# Remote_nodeIO_Hardware.net
KiCad netlist of a schematic drawn in EasyEDA Pro
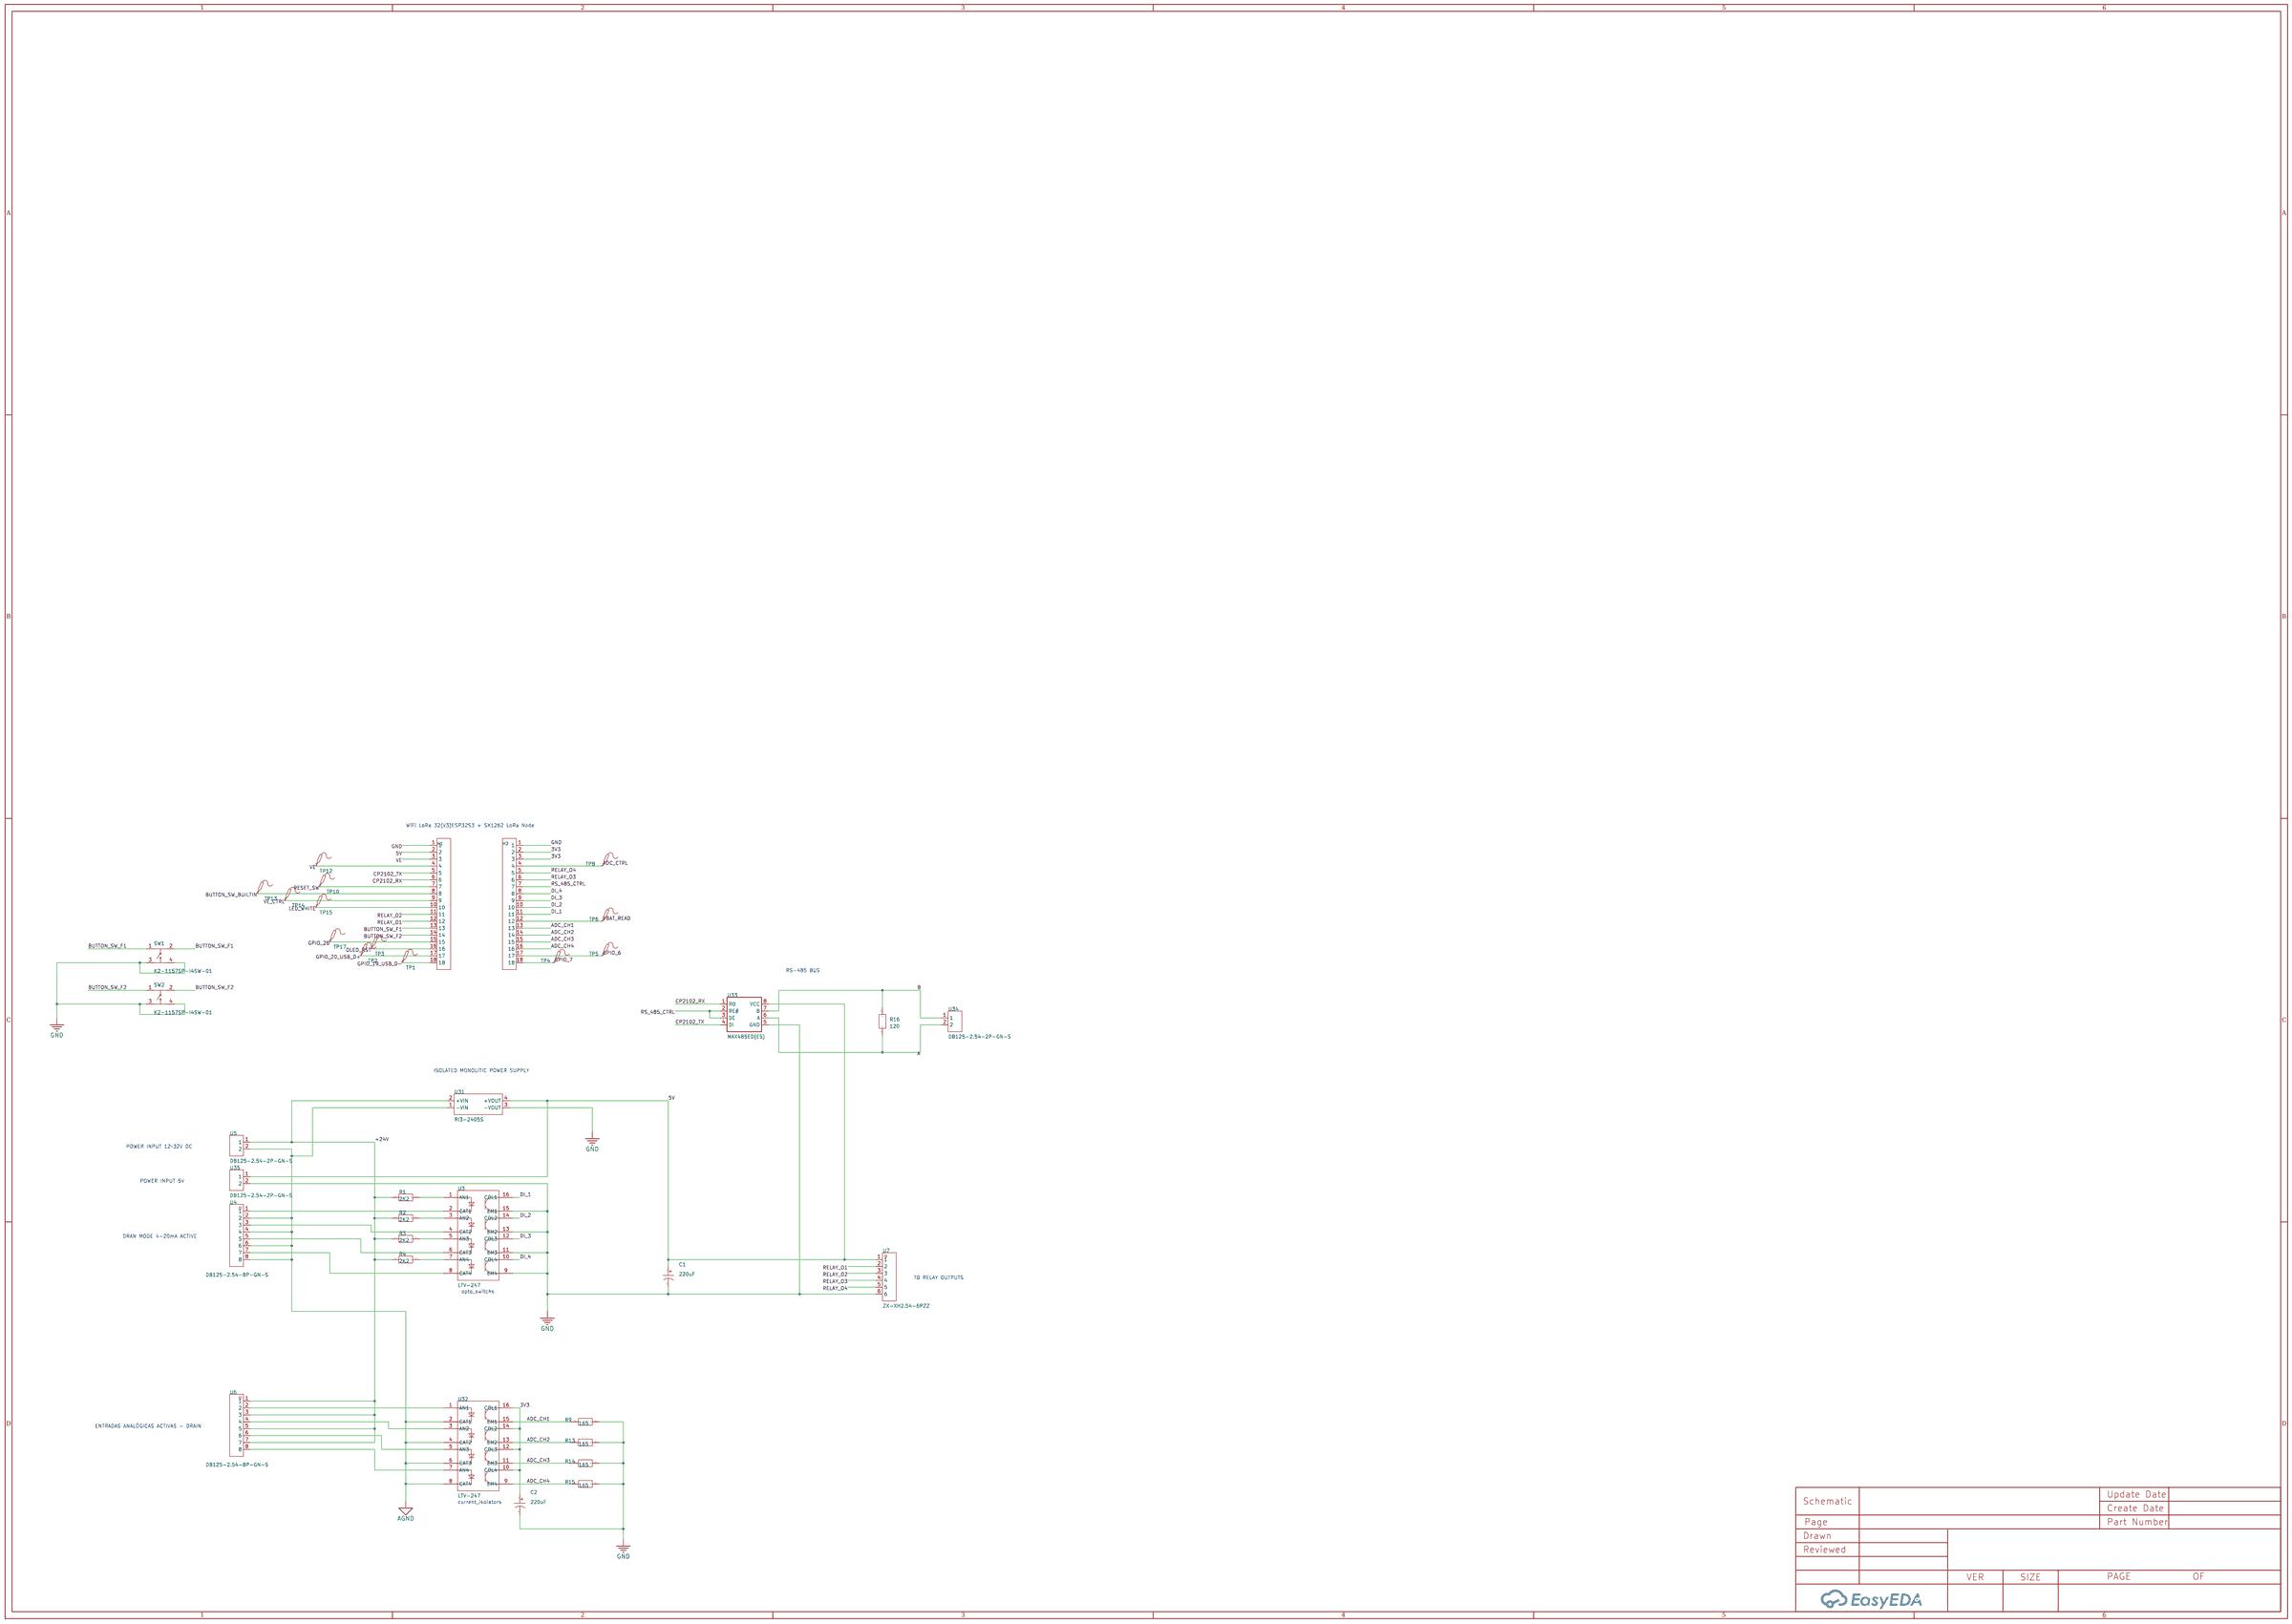
[diagram p0: schematic sheet]

(export (version "E")
  (design (tool "Eeschema 10.0.6"))
  (components
    (comp (ref "C1")
      (value "220uF")
      (footprint "easyedapro:CAP-SMD_BD6.3-L6.6-W6.6-FD")
      (fields (field (name "Manufacturer Part") "RVT1A221M0605") (field (name "Manufacturer") "ROQANG(容强)"))
      (libsource (lib "easyedapro") (part "RVT1A221M0605-C72494"))
    )
    (comp (ref "C2")
      (value "220uF")
      (footprint "easyedapro:CAP-SMD_BD6.3-L6.6-W6.6-FD")
      (fields (field (name "Manufacturer Part") "RVT1A221M0605") (field (name "Manufacturer") "ROQANG(容强)"))
      (libsource (lib "easyedapro") (part "RVT1A221M0605-C72494"))
    )
    (comp (ref "H1")
      (value "PM254-1-18-Z-8.5")
      (footprint "easyedapro:HDR-TH_18P-P2.54-V-F")
      (fields (field (name "Manufacturer") "HCTL(华灿天禄)"))
      (libsource (lib "easyedapro") (part "PM254-1-18-Z-8.5_C3012090"))
    )
    (comp (ref "H2")
      (value "PM254-1-18-Z-8.5")
      (footprint "easyedapro:HDR-TH_18P-P2.54-V-F")
      (fields (field (name "Manufacturer") "HCTL(华灿天禄)"))
      (libsource (lib "easyedapro") (part "PM254-1-18-Z-8.5_C3012090"))
    )
    (comp (ref "R1")
      (value "2K2")
      (footprint "easyedapro:R1206")
      (fields
        (field (name "Manufacturer Part") "AS0606J036JT5E")
        (field (name "Manufacturer") "UNI-ROYAL(厚声)")
      )
      (libsource (lib "easyedapro") (part "AS0606J036JT5E"))
    )
    (comp (ref "R2")
      (value "2K2")
      (footprint "easyedapro:R1206")
      (fields
        (field (name "Manufacturer Part") "AS0606J036JT5E")
        (field (name "Manufacturer") "UNI-ROYAL(厚声)")
      )
      (libsource (lib "easyedapro") (part "AS0606J036JT5E"))
    )
    (comp (ref "R3")
      (value "2K2")
      (footprint "easyedapro:R1206")
      (fields
        (field (name "Manufacturer Part") "AS0606J036JT5E")
        (field (name "Manufacturer") "UNI-ROYAL(厚声)")
      )
      (libsource (lib "easyedapro") (part "AS0606J036JT5E"))
    )
    (comp (ref "R4")
      (value "2K2")
      (footprint "easyedapro:R1206")
      (fields
        (field (name "Manufacturer Part") "AS0606J036JT5E")
        (field (name "Manufacturer") "UNI-ROYAL(厚声)")
      )
      (libsource (lib "easyedapro") (part "AS0606J036JT5E"))
    )
    (comp (ref "R9")
      (value "165")
      (footprint "easyedapro:R1206")
      (fields
        (field (name "Manufacturer Part") "AS0606J036JT5E")
        (field (name "Manufacturer") "UNI-ROYAL(厚声)")
      )
      (libsource (lib "easyedapro") (part "AS0606J036JT5E"))
    )
    (comp (ref "R13")
      (value "165")
      (footprint "easyedapro:R1206")
      (fields
        (field (name "Manufacturer Part") "AS0606J036JT5E")
        (field (name "Manufacturer") "UNI-ROYAL(厚声)")
      )
      (libsource (lib "easyedapro") (part "AS0606J036JT5E"))
    )
    (comp (ref "R14")
      (value "165")
      (footprint "easyedapro:R1206")
      (fields
        (field (name "Manufacturer Part") "AS0606J036JT5E")
        (field (name "Manufacturer") "UNI-ROYAL(厚声)")
      )
      (libsource (lib "easyedapro") (part "AS0606J036JT5E"))
    )
    (comp (ref "R15")
      (value "165")
      (footprint "easyedapro:R1206")
      (fields
        (field (name "Manufacturer Part") "AS0606J036JT5E")
        (field (name "Manufacturer") "UNI-ROYAL(厚声)")
      )
      (libsource (lib "easyedapro") (part "AS0606J036JT5E"))
    )
    (comp (ref "R16")
      (value "120")
      (footprint "easyedapro:R1206")
      (fields
        (field (name "Manufacturer Part") "AS0606J036JT5E")
        (field (name "Manufacturer") "UNI-ROYAL(厚声)")
      )
      (libsource (lib "easyedapro") (part "AS0606J036JT5E"))
    )
    (comp (ref "SW1")
      (value "K2-1157SP-I4SW-01")
      (footprint "easyedapro:SW-SMD_4P-L6.2-W6.2-P4.50-LS8.6")
      (fields (field (name "Manufacturer") "韩国韩荣"))
      (libsource (lib "easyedapro") (part "K2-1157SP-I4SW-04"))
    )
    (comp (ref "SW2")
      (value "K2-1157SP-I4SW-01")
      (footprint "easyedapro:SW-SMD_4P-L6.2-W6.2-P4.50-LS8.6")
      (fields (field (name "Manufacturer") "韩国韩荣"))
      (libsource (lib "easyedapro") (part "K2-1157SP-I4SW-04"))
    )
    (comp (ref "TP1")
      (value "~")
      (footprint "easyedapro:Test-Point-0.5mm")
      (description "Test Point 测试点")
      (libsource (lib "easyedapro") (part "Test-Point"))
    )
    (comp (ref "TP2")
      (value "~")
      (footprint "easyedapro:Test-Point-0.5mm")
      (description "Test Point 测试点")
      (libsource (lib "easyedapro") (part "Test-Point"))
    )
    (comp (ref "TP3")
      (value "~")
      (footprint "easyedapro:Test-Point-0.5mm")
      (description "Test Point 测试点")
      (libsource (lib "easyedapro") (part "Test-Point"))
    )
    (comp (ref "TP4")
      (value "~")
      (footprint "easyedapro:Test-Point-0.5mm")
      (description "Test Point 测试点")
      (libsource (lib "easyedapro") (part "Test-Point"))
    )
    (comp (ref "TP5")
      (value "~")
      (footprint "easyedapro:Test-Point-0.5mm")
      (description "Test Point 测试点")
      (libsource (lib "easyedapro") (part "Test-Point"))
    )
    (comp (ref "TP6")
      (value "~")
      (footprint "easyedapro:Test-Point-0.5mm")
      (description "Test Point 测试点")
      (libsource (lib "easyedapro") (part "Test-Point"))
    )
    (comp (ref "TP8")
      (value "~")
      (footprint "easyedapro:Test-Point-0.5mm")
      (description "Test Point 测试点")
      (libsource (lib "easyedapro") (part "Test-Point"))
    )
    (comp (ref "TP10")
      (value "~")
      (footprint "easyedapro:Test-Point-0.5mm")
      (description "Test Point 测试点")
      (libsource (lib "easyedapro") (part "Test-Point"))
    )
    (comp (ref "TP12")
      (value "~")
      (footprint "easyedapro:Test-Point-0.5mm")
      (description "Test Point 测试点")
      (libsource (lib "easyedapro") (part "Test-Point"))
    )
    (comp (ref "TP13")
      (value "~")
      (footprint "easyedapro:Test-Point-0.5mm")
      (description "Test Point 测试点")
      (libsource (lib "easyedapro") (part "Test-Point"))
    )
    (comp (ref "TP14")
      (value "~")
      (footprint "easyedapro:Test-Point-0.5mm")
      (description "Test Point 测试点")
      (libsource (lib "easyedapro") (part "Test-Point"))
    )
    (comp (ref "TP15")
      (value "~")
      (footprint "easyedapro:Test-Point-0.5mm")
      (description "Test Point 测试点")
      (libsource (lib "easyedapro") (part "Test-Point"))
    )
    (comp (ref "TP17")
      (value "~")
      (footprint "easyedapro:Test-Point-0.5mm")
      (description "Test Point 测试点")
      (libsource (lib "easyedapro") (part "Test-Point"))
    )
    (comp (ref "U3")
      (value "LTV-247")
      (footprint "easyedapro:SOP-16_L10.3-W5.4-P1.27-LS7.8-BL")
      (fields (field (name "Manufacturer") "LITEON(光宝)"))
      (libsource (lib "easyedapro") (part "LTV-247"))
    )
    (comp (ref "U4")
      (value "DB125-2.54-8P-GN-S")
      (footprint "easyedapro:CONN-TH_DB125-2.54-8P-GN")
      (fields (field (name "Manufacturer") "DORABO(地博电气)"))
      (libsource (lib "easyedapro") (part "DB125-2.54-8P-GN"))
    )
    (comp (ref "U5")
      (value "DB125-2.54-2P-GN-S")
      (footprint "easyedapro:CONN-TH_DB125-2.54-2P-GN")
      (fields (field (name "Manufacturer") "DORABO(地博电气)"))
      (libsource (lib "easyedapro") (part "DB125-2.54-2P-GN"))
    )
    (comp (ref "U6")
      (value "DB125-2.54-8P-GN-S")
      (footprint "easyedapro:CONN-TH_DB125-2.54-8P-GN")
      (fields (field (name "Manufacturer") "DORABO(地博电气)"))
      (libsource (lib "easyedapro") (part "DB125-2.54-8P-GN"))
    )
    (comp (ref "U7")
      (value "ZX-XH2.54-6PZZ")
      (footprint "easyedapro:CONN-TH_6P-P2.50_ZX-XH2.54-6PZZ")
      (fields (field (name "Manufacturer") "Megastar(兆星)"))
      (libsource (lib "easyedapro") (part "ZX-XH2.54-6PZZ"))
    )
    (comp (ref "U31")
      (value "RI3-2405S")
      (footprint "easyedapro:PWRM-TH_RI3-XXXXS")
      (fields (field (name "Manufacturer") "Recom Power"))
      (libsource (lib "easyedapro") (part "RI3-2405S"))
    )
    (comp (ref "U32")
      (value "LTV-247")
      (footprint "easyedapro:SOP-16_L10.3-W5.4-P1.27-LS7.8-BL")
      (fields (field (name "Manufacturer") "LITEON(光宝)"))
      (libsource (lib "easyedapro") (part "LTV-247"))
    )
    (comp (ref "U33")
      (value "MAX485ED(ES)")
      (footprint "easyedapro:SOIC-8_L5.0-W4.0-P1.27-LS6.0-BL")
      (fields (field (name "Manufacturer") "ElecSuper(静芯)"))
      (libsource (lib "easyedapro") (part "MAX485ED(ES)"))
    )
    (comp (ref "U34")
      (value "DB125-2.54-2P-GN-S")
      (footprint "easyedapro:CONN-TH_DB125-2.54-2P-GN")
      (fields (field (name "Manufacturer") "DORABO(地博电气)"))
      (libsource (lib "easyedapro") (part "DB125-2.54-2P-GN"))
    )
    (comp (ref "U35")
      (value "DB125-2.54-2P-GN-S")
      (footprint "easyedapro:CONN-TH_DB125-2.54-2P-GN")
      (fields (field (name "Manufacturer") "DORABO(地博电气)"))
      (libsource (lib "easyedapro") (part "DB125-2.54-2P-GN"))
    )
  )
  (nets
    (net (code "1") (name "/+24V") (class "Default")
      (node (ref "R1") (pin "1") (pinfunction "1_1") (pintype "unspecified"))
      (node (ref "R2") (pin "1") (pinfunction "1_1") (pintype "unspecified"))
      (node (ref "R3") (pin "1") (pinfunction "1_1") (pintype "unspecified"))
      (node (ref "R4") (pin "1") (pinfunction "1_1") (pintype "unspecified"))
      (node (ref "U31") (pin "2") (pinfunction "+VIN_2") (pintype "unspecified"))
      (node (ref "U5") (pin "1") (pinfunction "1_1") (pintype "unspecified"))
      (node (ref "U6") (pin "1") (pinfunction "1_1") (pintype "unspecified"))
      (node (ref "U6") (pin "3") (pinfunction "3_3") (pintype "unspecified"))
      (node (ref "U6") (pin "5") (pinfunction "5_5") (pintype "unspecified"))
      (node (ref "U6") (pin "7") (pinfunction "7_7") (pintype "unspecified"))
    )
    (net (code "2") (name "/3V3") (class "Default")
      (node (ref "C2") (pin "1") (pinfunction "1_1") (pintype "input"))
      (node (ref "H2") (pin "2") (pinfunction "2_2") (pintype "unspecified"))
      (node (ref "H2") (pin "3") (pinfunction "3_3") (pintype "unspecified"))
      (node (ref "U32") (pin "10") (pinfunction "COL4_10") (pintype "unspecified"))
      (node (ref "U32") (pin "12") (pinfunction "COL3_12") (pintype "unspecified"))
      (node (ref "U32") (pin "14") (pinfunction "COL2_14") (pintype "unspecified"))
      (node (ref "U32") (pin "16") (pinfunction "COL1_16") (pintype "unspecified"))
    )
    (net (code "3") (name "/5V") (class "Default")
      (node (ref "C1") (pin "1") (pinfunction "1_1") (pintype "input"))
      (node (ref "H1") (pin "2") (pinfunction "2_2") (pintype "unspecified"))
      (node (ref "U31") (pin "4") (pinfunction "+VOUT_4") (pintype "unspecified"))
      (node (ref "U33") (pin "8") (pinfunction "VCC_8") (pintype "unspecified"))
      (node (ref "U35") (pin "1") (pinfunction "1_1") (pintype "unspecified"))
      (node (ref "U7") (pin "1") (pinfunction "1_1") (pintype "unspecified"))
    )
    (net (code "4") (name "/A") (class "Default")
      (node (ref "R16") (pin "1") (pinfunction "1_1") (pintype "unspecified"))
      (node (ref "U33") (pin "6") (pinfunction "A_6") (pintype "unspecified"))
      (node (ref "U34") (pin "2") (pinfunction "2_2") (pintype "unspecified"))
    )
    (net (code "5") (name "/ADC_CH1") (class "Default")
      (node (ref "H2") (pin "13") (pinfunction "13_13") (pintype "unspecified"))
      (node (ref "R9") (pin "1") (pinfunction "1_1") (pintype "unspecified"))
      (node (ref "U32") (pin "15") (pinfunction "EM1_15") (pintype "unspecified"))
    )
    (net (code "6") (name "/ADC_CH2") (class "Default")
      (node (ref "H2") (pin "14") (pinfunction "14_14") (pintype "unspecified"))
      (node (ref "R13") (pin "1") (pinfunction "1_1") (pintype "unspecified"))
      (node (ref "U32") (pin "13") (pinfunction "EM2_13") (pintype "unspecified"))
    )
    (net (code "7") (name "/ADC_CH3") (class "Default")
      (node (ref "H2") (pin "15") (pinfunction "15_15") (pintype "unspecified"))
      (node (ref "R14") (pin "1") (pinfunction "1_1") (pintype "unspecified"))
      (node (ref "U32") (pin "11") (pinfunction "EM3_11") (pintype "unspecified"))
    )
    (net (code "8") (name "/ADC_CH4") (class "Default")
      (node (ref "H2") (pin "16") (pinfunction "16_16") (pintype "unspecified"))
      (node (ref "R15") (pin "1") (pinfunction "1_1") (pintype "unspecified"))
      (node (ref "U32") (pin "9") (pinfunction "EM4_9") (pintype "unspecified"))
    )
    (net (code "9") (name "/ADC_CTRL") (class "Default")
      (node (ref "H2") (pin "4") (pinfunction "4_4") (pintype "unspecified"))
      (node (ref "TP8") (pin "1") (pinfunction "1_1") (pintype "unspecified"))
    )
    (net (code "10") (name "/B") (class "Default")
      (node (ref "R16") (pin "2") (pinfunction "2_2") (pintype "unspecified"))
      (node (ref "U33") (pin "7") (pinfunction "B_7") (pintype "unspecified"))
      (node (ref "U34") (pin "1") (pinfunction "1_1") (pintype "unspecified"))
    )
    (net (code "11") (name "/BUTTON_SW_BUILTIN") (class "Default")
      (node (ref "H1") (pin "8") (pinfunction "8_8") (pintype "unspecified"))
      (node (ref "TP13") (pin "1") (pinfunction "1_1") (pintype "unspecified"))
    )
    (net (code "12") (name "/BUTTON_SW_F1") (class "Default")
      (node (ref "H1") (pin "13") (pinfunction "13_13") (pintype "unspecified"))
      (node (ref "SW1") (pin "1") (pinfunction "1_1") (pintype "unspecified"))
      (node (ref "SW1") (pin "2") (pinfunction "2_2") (pintype "unspecified"))
    )
    (net (code "13") (name "/BUTTON_SW_F2") (class "Default")
      (node (ref "H1") (pin "14") (pinfunction "14_14") (pintype "unspecified"))
      (node (ref "SW2") (pin "1") (pinfunction "1_1") (pintype "unspecified"))
      (node (ref "SW2") (pin "2") (pinfunction "2_2") (pintype "unspecified"))
    )
    (net (code "14") (name "/CP2102_RX") (class "Default")
      (node (ref "H1") (pin "6") (pinfunction "6_6") (pintype "unspecified"))
      (node (ref "U33") (pin "1") (pinfunction "RO_1") (pintype "unspecified"))
    )
    (net (code "15") (name "/CP2102_TX") (class "Default")
      (node (ref "H1") (pin "5") (pinfunction "5_5") (pintype "unspecified"))
      (node (ref "U33") (pin "4") (pinfunction "DI_4") (pintype "unspecified"))
    )
    (net (code "16") (name "/DI_1") (class "Default")
      (node (ref "H2") (pin "11") (pinfunction "11_11") (pintype "unspecified"))
      (node (ref "U3") (pin "16") (pinfunction "COL1_16") (pintype "unspecified"))
    )
    (net (code "17") (name "/DI_2") (class "Default")
      (node (ref "H2") (pin "10") (pinfunction "10_10") (pintype "unspecified"))
      (node (ref "U3") (pin "14") (pinfunction "COL2_14") (pintype "unspecified"))
    )
    (net (code "18") (name "/DI_3") (class "Default")
      (node (ref "H2") (pin "9") (pinfunction "9_9") (pintype "unspecified"))
      (node (ref "U3") (pin "12") (pinfunction "COL3_12") (pintype "unspecified"))
    )
    (net (code "19") (name "/DI_4") (class "Default")
      (node (ref "H2") (pin "8") (pinfunction "8_8") (pintype "unspecified"))
      (node (ref "U3") (pin "10") (pinfunction "COL4_10") (pintype "unspecified"))
    )
    (net (code "20") (name "/GPIO_6") (class "Default")
      (node (ref "H2") (pin "17") (pinfunction "17_17") (pintype "unspecified"))
      (node (ref "TP5") (pin "1") (pinfunction "1_1") (pintype "unspecified"))
    )
    (net (code "21") (name "/GPIO_7") (class "Default")
      (node (ref "H2") (pin "18") (pinfunction "18_18") (pintype "unspecified"))
      (node (ref "TP4") (pin "1") (pinfunction "1_1") (pintype "unspecified"))
    )
    (net (code "22") (name "/GPIO_19_USB_D-") (class "Default")
      (node (ref "H1") (pin "18") (pinfunction "18_18") (pintype "unspecified"))
      (node (ref "TP1") (pin "1") (pinfunction "1_1") (pintype "unspecified"))
    )
    (net (code "23") (name "/GPIO_20_USB_D+") (class "Default")
      (node (ref "H1") (pin "17") (pinfunction "17_17") (pintype "unspecified"))
      (node (ref "TP2") (pin "1") (pinfunction "1_1") (pintype "unspecified"))
    )
    (net (code "24") (name "/GPIO_26") (class "Default")
      (node (ref "H1") (pin "15") (pinfunction "15_15") (pintype "unspecified"))
      (node (ref "TP17") (pin "1") (pinfunction "1_1") (pintype "unspecified"))
    )
    (net (code "25") (name "/LED_WHITE") (class "Default")
      (node (ref "H1") (pin "10") (pinfunction "10_10") (pintype "unspecified"))
      (node (ref "TP15") (pin "1") (pinfunction "1_1") (pintype "unspecified"))
    )
    (net (code "26") (name "/OLED_RST") (class "Default")
      (node (ref "H1") (pin "16") (pinfunction "16_16") (pintype "unspecified"))
      (node (ref "TP3") (pin "1") (pinfunction "1_1") (pintype "unspecified"))
    )
    (net (code "27") (name "/RELAY_O1") (class "Default")
      (node (ref "H1") (pin "12") (pinfunction "12_12") (pintype "unspecified"))
      (node (ref "U7") (pin "2") (pinfunction "2_2") (pintype "unspecified"))
    )
    (net (code "28") (name "/RELAY_O2") (class "Default")
      (node (ref "H1") (pin "11") (pinfunction "11_11") (pintype "unspecified"))
      (node (ref "U7") (pin "3") (pinfunction "3_3") (pintype "unspecified"))
    )
    (net (code "29") (name "/RELAY_O3") (class "Default")
      (node (ref "H2") (pin "6") (pinfunction "6_6") (pintype "unspecified"))
      (node (ref "U7") (pin "4") (pinfunction "4_4") (pintype "unspecified"))
    )
    (net (code "30") (name "/RELAY_O4") (class "Default")
      (node (ref "H2") (pin "5") (pinfunction "5_5") (pintype "unspecified"))
      (node (ref "U7") (pin "5") (pinfunction "5_5") (pintype "unspecified"))
    )
    (net (code "31") (name "/RESET_SW") (class "Default")
      (node (ref "H1") (pin "7") (pinfunction "7_7") (pintype "unspecified"))
      (node (ref "TP10") (pin "1") (pinfunction "1_1") (pintype "unspecified"))
    )
    (net (code "32") (name "/RS_485_CTRL") (class "Default")
      (node (ref "H2") (pin "7") (pinfunction "7_7") (pintype "unspecified"))
      (node (ref "U33") (pin "2") (pinfunction "RE#_2") (pintype "unspecified"))
      (node (ref "U33") (pin "3") (pinfunction "DE_3") (pintype "unspecified"))
    )
    (net (code "33") (name "/VBAT_READ") (class "Default")
      (node (ref "H2") (pin "12") (pinfunction "12_12") (pintype "unspecified"))
      (node (ref "TP6") (pin "1") (pinfunction "1_1") (pintype "unspecified"))
    )
    (net (code "34") (name "/VE") (class "Default")
      (node (ref "H1") (pin "3") (pinfunction "3_3") (pintype "unspecified"))
      (node (ref "H1") (pin "4") (pinfunction "4_4") (pintype "unspecified"))
      (node (ref "TP12") (pin "1") (pinfunction "1_1") (pintype "unspecified"))
    )
    (net (code "35") (name "/VE_CTRL") (class "Default")
      (node (ref "H1") (pin "9") (pinfunction "9_9") (pintype "unspecified"))
      (node (ref "TP14") (pin "1") (pinfunction "1_1") (pintype "unspecified"))
    )
    (net (code "36") (name "AGND") (class "Default")
      (node (ref "U31") (pin "1") (pinfunction "-VIN_1") (pintype "unspecified"))
      (node (ref "U32") (pin "2") (pinfunction "CAT1_2") (pintype "unspecified"))
      (node (ref "U32") (pin "4") (pinfunction "CAT2_4") (pintype "unspecified"))
      (node (ref "U32") (pin "6") (pinfunction "CAT3_6") (pintype "unspecified"))
      (node (ref "U32") (pin "8") (pinfunction "CAT4_8") (pintype "unspecified"))
      (node (ref "U4") (pin "2") (pinfunction "2_2") (pintype "unspecified"))
      (node (ref "U4") (pin "4") (pinfunction "4_4") (pintype "unspecified"))
      (node (ref "U4") (pin "6") (pinfunction "6_6") (pintype "unspecified"))
      (node (ref "U4") (pin "8") (pinfunction "8_8") (pintype "unspecified"))
      (node (ref "U5") (pin "2") (pinfunction "2_2") (pintype "unspecified"))
    )
    (net (code "37") (name "GND") (class "Default")
      (node (ref "C1") (pin "2") (pinfunction "2_2") (pintype "input"))
      (node (ref "C2") (pin "2") (pinfunction "2_2") (pintype "input"))
      (node (ref "H1") (pin "1") (pinfunction "1_1") (pintype "unspecified"))
      (node (ref "H2") (pin "1") (pinfunction "1_1") (pintype "unspecified"))
      (node (ref "R13") (pin "2") (pinfunction "2_2") (pintype "unspecified"))
      (node (ref "R14") (pin "2") (pinfunction "2_2") (pintype "unspecified"))
      (node (ref "R15") (pin "2") (pinfunction "2_2") (pintype "unspecified"))
      (node (ref "R9") (pin "2") (pinfunction "2_2") (pintype "unspecified"))
      (node (ref "SW1") (pin "3") (pinfunction "3_3") (pintype "unspecified"))
      (node (ref "SW1") (pin "4") (pinfunction "4_4") (pintype "unspecified"))
      (node (ref "SW2") (pin "3") (pinfunction "3_3") (pintype "unspecified"))
      (node (ref "SW2") (pin "4") (pinfunction "4_4") (pintype "unspecified"))
      (node (ref "U3") (pin "11") (pinfunction "EM3_11") (pintype "unspecified"))
      (node (ref "U3") (pin "13") (pinfunction "EM2_13") (pintype "unspecified"))
      (node (ref "U3") (pin "15") (pinfunction "EM1_15") (pintype "unspecified"))
      (node (ref "U3") (pin "9") (pinfunction "EM4_9") (pintype "unspecified"))
      (node (ref "U31") (pin "3") (pinfunction "-VOUT_3") (pintype "unspecified"))
      (node (ref "U33") (pin "5") (pinfunction "GND_5") (pintype "unspecified"))
      (node (ref "U35") (pin "2") (pinfunction "2_2") (pintype "unspecified"))
      (node (ref "U7") (pin "6") (pinfunction "6_6") (pintype "unspecified"))
    )
    (net (code "38") (name "Net-(U3-AN1)") (class "Default")
      (node (ref "R1") (pin "2") (pinfunction "2_2") (pintype "unspecified"))
      (node (ref "U3") (pin "1") (pinfunction "AN1_1") (pintype "unspecified"))
    )
    (net (code "39") (name "Net-(U3-AN2)") (class "Default")
      (node (ref "R2") (pin "2") (pinfunction "2_2") (pintype "unspecified"))
      (node (ref "U3") (pin "3") (pinfunction "AN2_3") (pintype "unspecified"))
    )
    (net (code "40") (name "Net-(U3-AN3)") (class "Default")
      (node (ref "R3") (pin "2") (pinfunction "2_2") (pintype "unspecified"))
      (node (ref "U3") (pin "5") (pinfunction "AN3_5") (pintype "unspecified"))
    )
    (net (code "41") (name "Net-(U3-AN4)") (class "Default")
      (node (ref "R4") (pin "2") (pinfunction "2_2") (pintype "unspecified"))
      (node (ref "U3") (pin "7") (pinfunction "AN4_7") (pintype "unspecified"))
    )
    (net (code "42") (name "Net-(U3-CAT1)") (class "Default")
      (node (ref "U3") (pin "2") (pinfunction "CAT1_2") (pintype "unspecified"))
      (node (ref "U4") (pin "1") (pinfunction "1_1") (pintype "unspecified"))
    )
    (net (code "43") (name "Net-(U3-CAT2)") (class "Default")
      (node (ref "U3") (pin "4") (pinfunction "CAT2_4") (pintype "unspecified"))
      (node (ref "U4") (pin "3") (pinfunction "3_3") (pintype "unspecified"))
    )
    (net (code "44") (name "Net-(U3-CAT3)") (class "Default")
      (node (ref "U3") (pin "6") (pinfunction "CAT3_6") (pintype "unspecified"))
      (node (ref "U4") (pin "5") (pinfunction "5_5") (pintype "unspecified"))
    )
    (net (code "45") (name "Net-(U3-CAT4)") (class "Default")
      (node (ref "U3") (pin "8") (pinfunction "CAT4_8") (pintype "unspecified"))
      (node (ref "U4") (pin "7") (pinfunction "7_7") (pintype "unspecified"))
    )
    (net (code "46") (name "Net-(U32-AN1)") (class "Default")
      (node (ref "U32") (pin "1") (pinfunction "AN1_1") (pintype "unspecified"))
      (node (ref "U6") (pin "2") (pinfunction "2_2") (pintype "unspecified"))
    )
    (net (code "47") (name "Net-(U32-AN2)") (class "Default")
      (node (ref "U32") (pin "3") (pinfunction "AN2_3") (pintype "unspecified"))
      (node (ref "U6") (pin "4") (pinfunction "4_4") (pintype "unspecified"))
    )
    (net (code "48") (name "Net-(U32-AN3)") (class "Default")
      (node (ref "U32") (pin "5") (pinfunction "AN3_5") (pintype "unspecified"))
      (node (ref "U6") (pin "6") (pinfunction "6_6") (pintype "unspecified"))
    )
    (net (code "49") (name "Net-(U32-AN4)") (class "Default")
      (node (ref "U32") (pin "7") (pinfunction "AN4_7") (pintype "unspecified"))
      (node (ref "U6") (pin "8") (pinfunction "8_8") (pintype "unspecified"))
    )
  )
)
